# FinalUSB.net
KiCad netlist of a schematic drawn in EasyEDA Pro
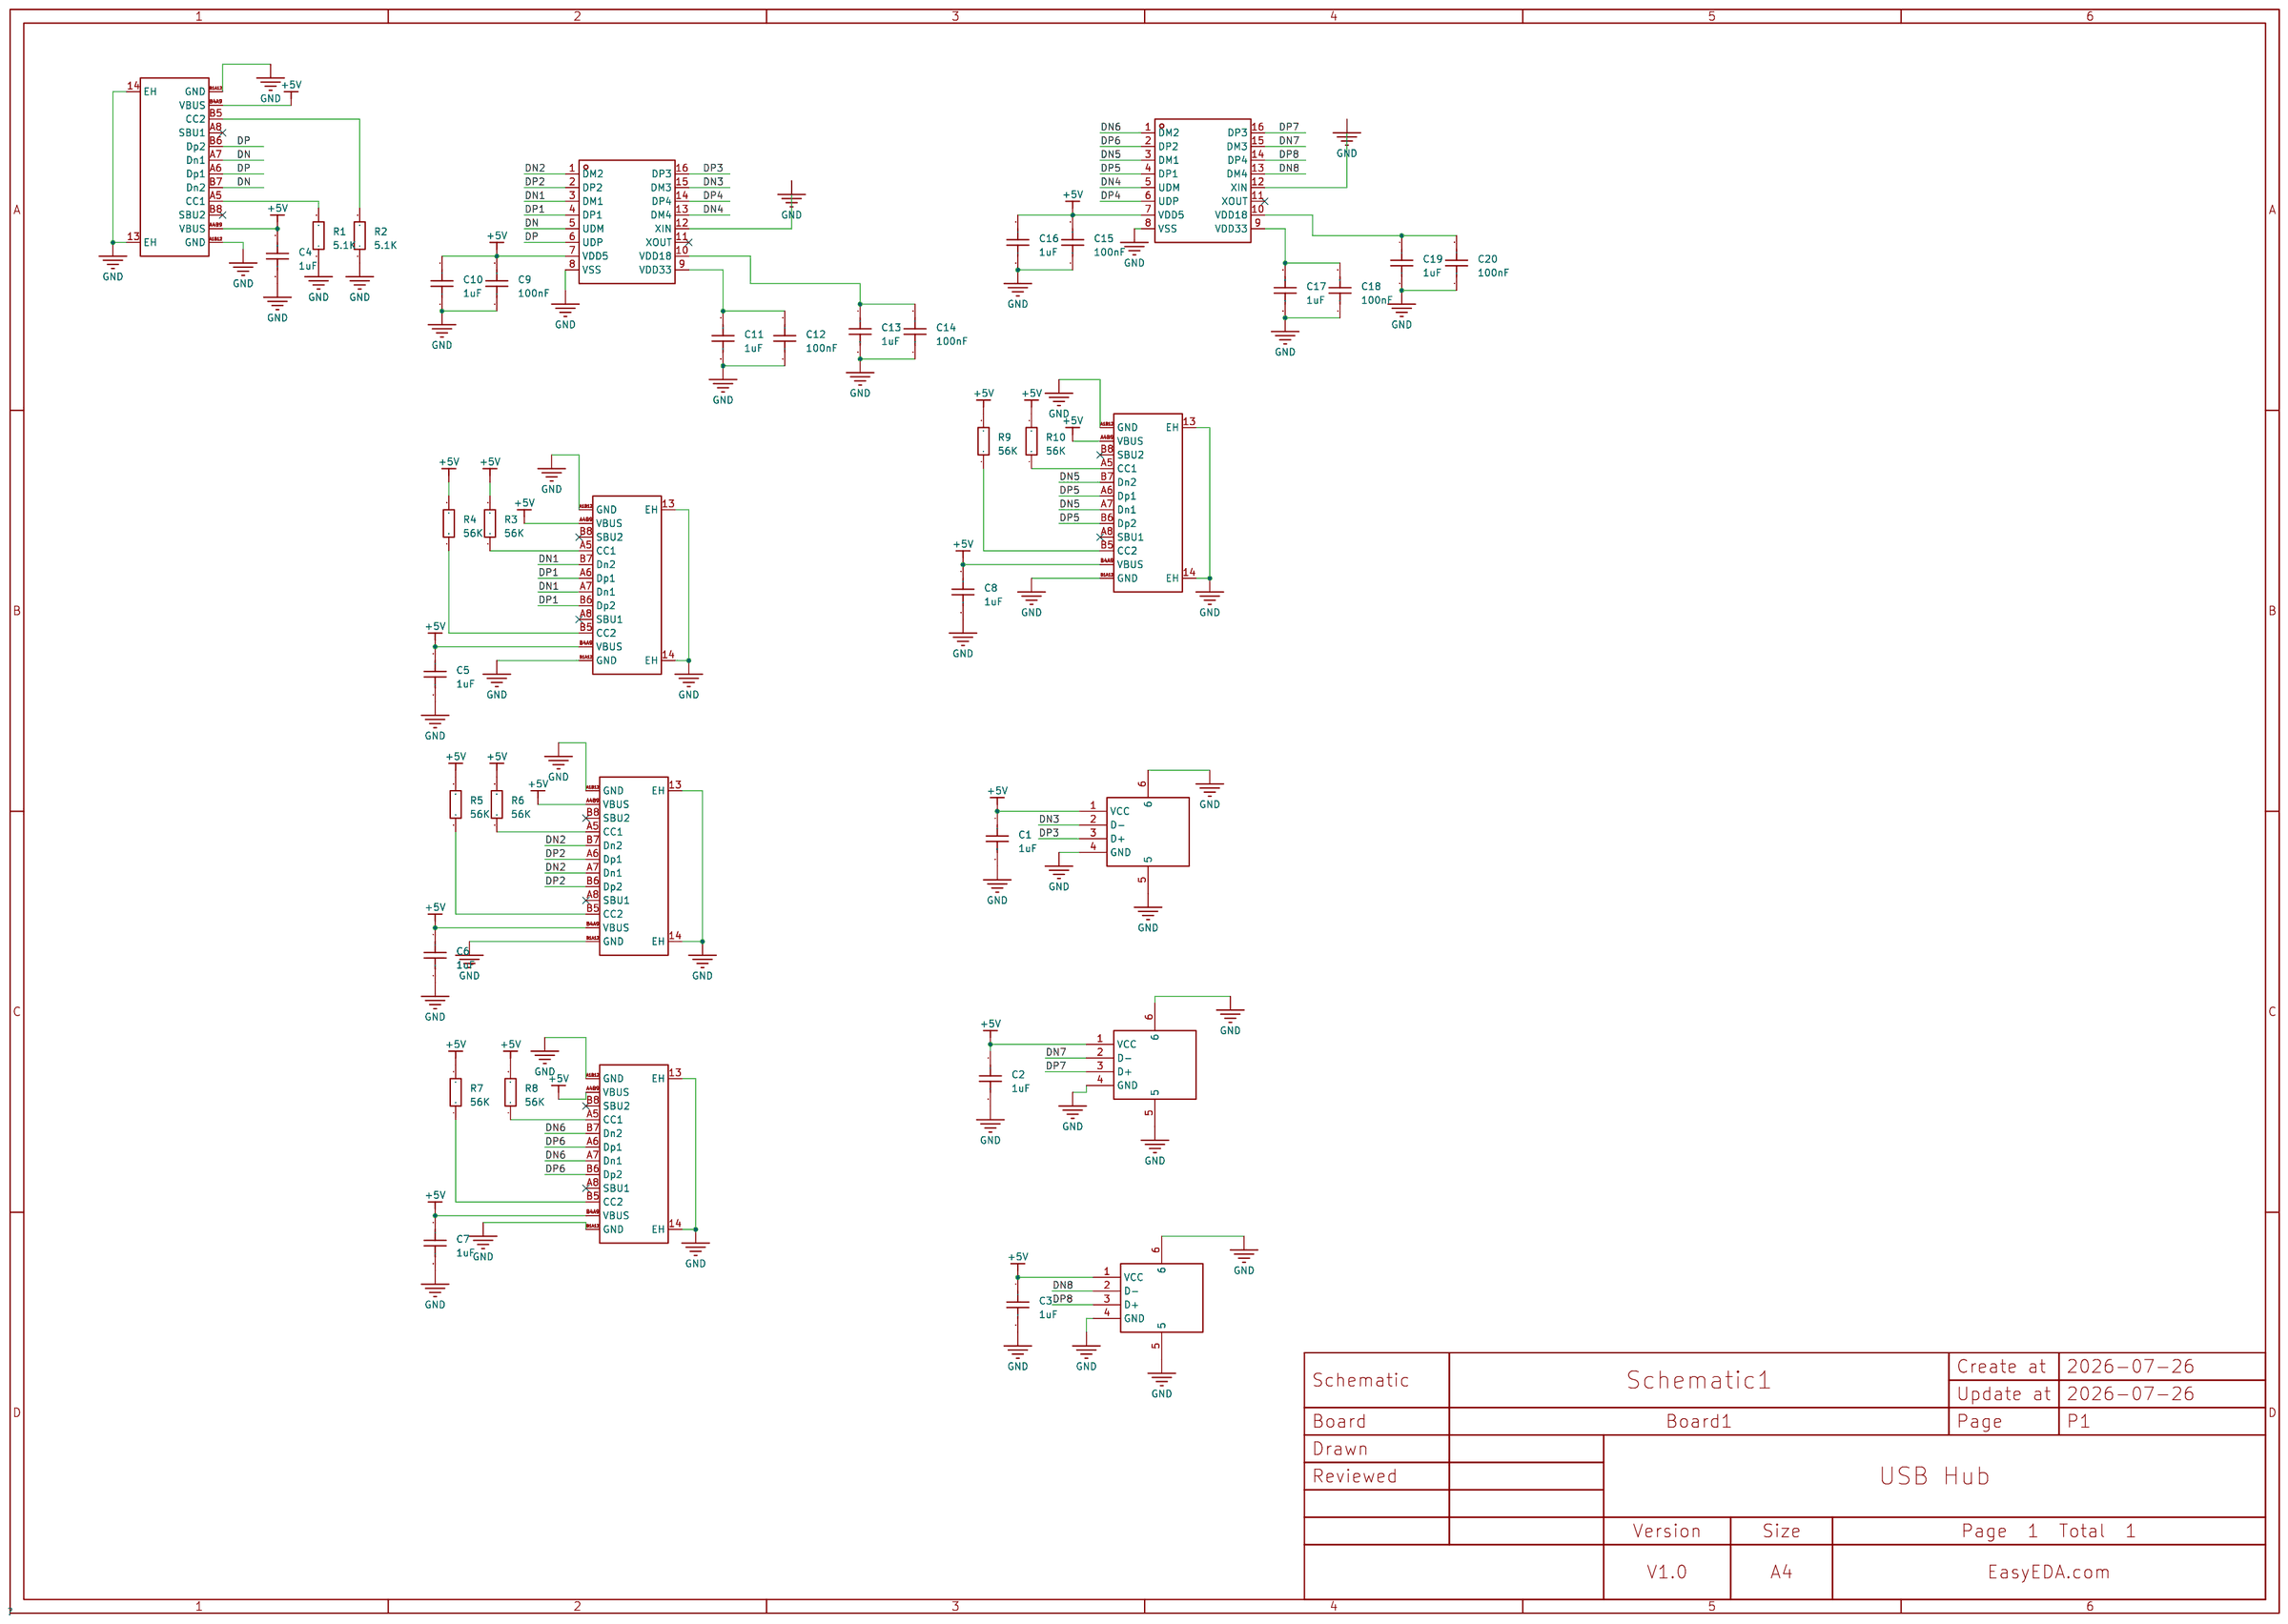
[diagram p0: schematic sheet]

(export (version "E")
  (design (tool "Eeschema 10.0.6"))
  (components
    (comp (ref "C1")
      (value "1uF")
      (footprint "easyedapro:C0603")
      (libsource (lib "easyedapro") (part "CAP_OLD"))
    )
    (comp (ref "C2")
      (value "1uF")
      (footprint "easyedapro:C0603")
      (libsource (lib "easyedapro") (part "CAP_OLD"))
    )
    (comp (ref "C3")
      (value "1uF")
      (footprint "easyedapro:C0603")
      (libsource (lib "easyedapro") (part "CAP_OLD"))
    )
    (comp (ref "C4")
      (value "1uF")
      (footprint "easyedapro:C0603")
      (libsource (lib "easyedapro") (part "CAP_OLD"))
    )
    (comp (ref "C5")
      (value "1uF")
      (footprint "easyedapro:C0603")
      (libsource (lib "easyedapro") (part "CAP_OLD"))
    )
    (comp (ref "C6")
      (value "1uF")
      (footprint "easyedapro:C0603")
      (libsource (lib "easyedapro") (part "CAP_OLD"))
    )
    (comp (ref "C7")
      (value "1uF")
      (footprint "easyedapro:C0603")
      (libsource (lib "easyedapro") (part "CAP_OLD"))
    )
    (comp (ref "C8")
      (value "1uF")
      (footprint "easyedapro:C0603")
      (libsource (lib "easyedapro") (part "CAP_OLD"))
    )
    (comp (ref "C9")
      (value "100nF")
      (footprint "easyedapro:C0603")
      (libsource (lib "easyedapro") (part "CAP_OLD"))
    )
    (comp (ref "C10")
      (value "1uF")
      (footprint "easyedapro:C0603")
      (libsource (lib "easyedapro") (part "CAP_OLD"))
    )
    (comp (ref "C11")
      (value "1uF")
      (footprint "easyedapro:C0603")
      (libsource (lib "easyedapro") (part "CAP_OLD"))
    )
    (comp (ref "C12")
      (value "100nF")
      (footprint "easyedapro:C0603")
      (libsource (lib "easyedapro") (part "CAP_OLD"))
    )
    (comp (ref "C13")
      (value "1uF")
      (footprint "easyedapro:C0603")
      (libsource (lib "easyedapro") (part "CAP_OLD"))
    )
    (comp (ref "C14")
      (value "100nF")
      (footprint "easyedapro:C0603")
      (libsource (lib "easyedapro") (part "CAP_OLD"))
    )
    (comp (ref "C15")
      (value "100nF")
      (footprint "easyedapro:C0603")
      (libsource (lib "easyedapro") (part "CAP_OLD"))
    )
    (comp (ref "C16")
      (value "1uF")
      (footprint "easyedapro:C0603")
      (libsource (lib "easyedapro") (part "CAP_OLD"))
    )
    (comp (ref "C17")
      (value "1uF")
      (footprint "easyedapro:C0603")
      (libsource (lib "easyedapro") (part "CAP_OLD"))
    )
    (comp (ref "C18")
      (value "100nF")
      (footprint "easyedapro:C0603")
      (libsource (lib "easyedapro") (part "CAP_OLD"))
    )
    (comp (ref "C19")
      (value "1uF")
      (footprint "easyedapro:C0603")
      (libsource (lib "easyedapro") (part "CAP_OLD"))
    )
    (comp (ref "C20")
      (value "100nF")
      (footprint "easyedapro:C0603")
      (libsource (lib "easyedapro") (part "CAP_OLD"))
    )
    (comp (ref "R1")
      (value "5.1K")
      (footprint "easyedapro:R0603")
      (libsource (lib "easyedapro") (part "Res"))
    )
    (comp (ref "R2")
      (value "5.1K")
      (footprint "easyedapro:R0603")
      (libsource (lib "easyedapro") (part "Res"))
    )
    (comp (ref "R3") (value "56K") (footprint "easyedapro:R0603") (libsource (lib "easyedapro") (part "Res")))
    (comp (ref "R4") (value "56K") (footprint "easyedapro:R0603") (libsource (lib "easyedapro") (part "Res")))
    (comp (ref "R5") (value "56K") (footprint "easyedapro:R0603") (libsource (lib "easyedapro") (part "Res")))
    (comp (ref "R6") (value "56K") (footprint "easyedapro:R0603") (libsource (lib "easyedapro") (part "Res")))
    (comp (ref "R7") (value "56K") (footprint "easyedapro:R0603") (libsource (lib "easyedapro") (part "Res")))
    (comp (ref "R8") (value "56K") (footprint "easyedapro:R0603") (libsource (lib "easyedapro") (part "Res")))
    (comp (ref "R9") (value "56K") (footprint "easyedapro:R0603") (libsource (lib "easyedapro") (part "Res")))
    (comp (ref "R10")
      (value "56K")
      (footprint "easyedapro:R0603")
      (libsource (lib "easyedapro") (part "Res"))
    )
    (comp (ref "U1")
      (value "SL2.1s")
      (footprint "easyedapro:SSOP-16_L4.6-W2.6-P0.53-LS4.0-BL")
      (fields (field (name "Manufacturer") "CoreChips(和芯润德)"))
      (libsource (lib "easyedapro") (part "SL2.1S"))
    )
    (comp (ref "U2")
      (value "SL2.1s")
      (footprint "easyedapro:SSOP-16_L4.6-W2.6-P0.53-LS4.0-BL")
      (fields (field (name "Manufacturer") "CoreChips(和芯润德)"))
      (libsource (lib "easyedapro") (part "SL2.1S"))
    )
    (comp (ref "USB1")
      (value "TYPE-C 16PIN 2MD(073)")
      (footprint "easyedapro:USB-C-SMD_TYPE-C-16PIN-2MD-073")
      (fields (field (name "Manufacturer") "SHOU HAN(首韩)"))
      (libsource (lib "easyedapro") (part "TYPE-C 16PIN 2MD(073)"))
    )
    (comp (ref "USB2")
      (value "TYPE-C 16PIN 2MD(073)")
      (footprint "easyedapro:USB-C-SMD_TYPE-C-16PIN-2MD-073")
      (fields (field (name "Manufacturer") "SHOU HAN(首韩)"))
      (libsource (lib "easyedapro") (part "TYPE-C 16PIN 2MD(073)"))
    )
    (comp (ref "USB3")
      (value "TYPE-C 16PIN 2MD(073)")
      (footprint "easyedapro:USB-C-SMD_TYPE-C-16PIN-2MD-073")
      (fields (field (name "Manufacturer") "SHOU HAN(首韩)"))
      (libsource (lib "easyedapro") (part "TYPE-C 16PIN 2MD(073)"))
    )
    (comp (ref "USB4")
      (value "10.0 QHHTZB6.3")
      (footprint "easyedapro:USB-A-TH_10.0QHHTZB6.3")
      (fields (field (name "Manufacturer") "SHOU HAN(首韩)"))
      (libsource (lib "easyedapro") (part "10.0 QHHTZB6.3"))
    )
    (comp (ref "USB5")
      (value "TYPE-C 16PIN 2MD(073)")
      (footprint "easyedapro:USB-C-SMD_TYPE-C-16PIN-2MD-073")
      (fields (field (name "Manufacturer") "SHOU HAN(首韩)"))
      (libsource (lib "easyedapro") (part "TYPE-C 16PIN 2MD(073)"))
    )
    (comp (ref "USB6")
      (value "10.0 QHHTZB6.3")
      (footprint "easyedapro:USB-A-TH_10.0QHHTZB6.3")
      (fields (field (name "Manufacturer") "SHOU HAN(首韩)"))
      (libsource (lib "easyedapro") (part "10.0 QHHTZB6.3"))
    )
    (comp (ref "USB7")
      (value "TYPE-C 16PIN 2MD(073)")
      (footprint "easyedapro:USB-C-SMD_TYPE-C-16PIN-2MD-073")
      (fields (field (name "Manufacturer") "SHOU HAN(首韩)"))
      (libsource (lib "easyedapro") (part "TYPE-C 16PIN 2MD(073)"))
    )
    (comp (ref "USB8")
      (value "10.0 QHHTZB6.3")
      (footprint "easyedapro:USB-A-TH_10.0QHHTZB6.3")
      (fields (field (name "Manufacturer") "SHOU HAN(首韩)"))
      (libsource (lib "easyedapro") (part "10.0 QHHTZB6.3"))
    )
  )
  (nets
    (net (code "1") (name "+5V") (class "Default")
      (node (ref "C1") (pin "1") (pinfunction "1_1") (pintype "input"))
      (node (ref "C10") (pin "1") (pinfunction "1_1") (pintype "input"))
      (node (ref "C15") (pin "2") (pinfunction "2_2") (pintype "input"))
      (node (ref "C16") (pin "1") (pinfunction "1_1") (pintype "input"))
      (node (ref "C2") (pin "1") (pinfunction "1_1") (pintype "input"))
      (node (ref "C3") (pin "1") (pinfunction "1_1") (pintype "input"))
      (node (ref "C4") (pin "1") (pinfunction "1_1") (pintype "input"))
      (node (ref "C5") (pin "1") (pinfunction "1_1") (pintype "input"))
      (node (ref "C6") (pin "1") (pinfunction "1_1") (pintype "input"))
      (node (ref "C7") (pin "1") (pinfunction "1_1") (pintype "input"))
      (node (ref "C8") (pin "1") (pinfunction "1_1") (pintype "input"))
      (node (ref "C9") (pin "2") (pinfunction "2_2") (pintype "input"))
      (node (ref "R10") (pin "2") (pinfunction "2_2") (pintype "input"))
      (node (ref "R3") (pin "2") (pinfunction "2_2") (pintype "input"))
      (node (ref "R4") (pin "2") (pinfunction "2_2") (pintype "input"))
      (node (ref "R5") (pin "2") (pinfunction "2_2") (pintype "input"))
      (node (ref "R6") (pin "2") (pinfunction "2_2") (pintype "input"))
      (node (ref "R7") (pin "2") (pinfunction "2_2") (pintype "input"))
      (node (ref "R8") (pin "2") (pinfunction "2_2") (pintype "input"))
      (node (ref "R9") (pin "2") (pinfunction "2_2") (pintype "input"))
      (node (ref "U1") (pin "7") (pinfunction "VDD5_7") (pintype "unspecified"))
      (node (ref "U2") (pin "7") (pinfunction "VDD5_7") (pintype "unspecified"))
      (node (ref "USB1") (pin "A4B9") (pinfunction "VBUS_A4B9") (pintype "unspecified"))
      (node (ref "USB1") (pin "B4A9") (pinfunction "VBUS_B4A9") (pintype "unspecified"))
      (node (ref "USB2") (pin "A4B9") (pinfunction "VBUS_A4B9") (pintype "unspecified"))
      (node (ref "USB2") (pin "B4A9") (pinfunction "VBUS_B4A9") (pintype "unspecified"))
      (node (ref "USB3") (pin "A4B9") (pinfunction "VBUS_A4B9") (pintype "unspecified"))
      (node (ref "USB3") (pin "B4A9") (pinfunction "VBUS_B4A9") (pintype "unspecified"))
      (node (ref "USB4") (pin "1") (pinfunction "VCC_1") (pintype "unspecified"))
      (node (ref "USB5") (pin "A4B9") (pinfunction "VBUS_A4B9") (pintype "unspecified"))
      (node (ref "USB5") (pin "B4A9") (pinfunction "VBUS_B4A9") (pintype "unspecified"))
      (node (ref "USB6") (pin "1") (pinfunction "VCC_1") (pintype "unspecified"))
      (node (ref "USB7") (pin "A4B9") (pinfunction "VBUS_A4B9") (pintype "unspecified"))
      (node (ref "USB7") (pin "B4A9") (pinfunction "VBUS_B4A9") (pintype "unspecified"))
      (node (ref "USB8") (pin "1") (pinfunction "VCC_1") (pintype "unspecified"))
    )
    (net (code "2") (name "/DN") (class "Default")
      (node (ref "U1") (pin "5") (pinfunction "UDM_5") (pintype "unspecified"))
      (node (ref "USB5") (pin "A7") (pinfunction "Dn1_A7") (pintype "unspecified"))
      (node (ref "USB5") (pin "B7") (pinfunction "Dn2_B7") (pintype "unspecified"))
    )
    (net (code "3") (name "/DN1") (class "Default")
      (node (ref "U1") (pin "3") (pinfunction "DM1_3") (pintype "unspecified"))
      (node (ref "USB1") (pin "A7") (pinfunction "Dn1_A7") (pintype "unspecified"))
      (node (ref "USB1") (pin "B7") (pinfunction "Dn2_B7") (pintype "unspecified"))
    )
    (net (code "4") (name "/DN2") (class "Default")
      (node (ref "U1") (pin "1") (pinfunction "DM2_1") (pintype "unspecified"))
      (node (ref "USB2") (pin "A7") (pinfunction "Dn1_A7") (pintype "unspecified"))
      (node (ref "USB2") (pin "B7") (pinfunction "Dn2_B7") (pintype "unspecified"))
    )
    (net (code "5") (name "/DN3") (class "Default")
      (node (ref "U1") (pin "15") (pinfunction "DM3_15") (pintype "unspecified"))
      (node (ref "USB6") (pin "2") (pinfunction "D-_2") (pintype "unspecified"))
    )
    (net (code "6") (name "/DN4") (class "Default")
      (node (ref "U1") (pin "13") (pinfunction "DM4_13") (pintype "unspecified"))
      (node (ref "U2") (pin "5") (pinfunction "UDM_5") (pintype "unspecified"))
    )
    (net (code "7") (name "/DN5") (class "Default")
      (node (ref "U2") (pin "3") (pinfunction "DM1_3") (pintype "unspecified"))
      (node (ref "USB7") (pin "A7") (pinfunction "Dn1_A7") (pintype "unspecified"))
      (node (ref "USB7") (pin "B7") (pinfunction "Dn2_B7") (pintype "unspecified"))
    )
    (net (code "8") (name "/DN6") (class "Default")
      (node (ref "U2") (pin "1") (pinfunction "DM2_1") (pintype "unspecified"))
      (node (ref "USB3") (pin "A7") (pinfunction "Dn1_A7") (pintype "unspecified"))
      (node (ref "USB3") (pin "B7") (pinfunction "Dn2_B7") (pintype "unspecified"))
    )
    (net (code "9") (name "/DN7") (class "Default")
      (node (ref "U2") (pin "15") (pinfunction "DM3_15") (pintype "unspecified"))
      (node (ref "USB4") (pin "2") (pinfunction "D-_2") (pintype "unspecified"))
    )
    (net (code "10") (name "/DN8") (class "Default")
      (node (ref "U2") (pin "13") (pinfunction "DM4_13") (pintype "unspecified"))
      (node (ref "USB8") (pin "2") (pinfunction "D-_2") (pintype "unspecified"))
    )
    (net (code "11") (name "/DP") (class "Default")
      (node (ref "U1") (pin "6") (pinfunction "UDP_6") (pintype "unspecified"))
      (node (ref "USB5") (pin "A6") (pinfunction "Dp1_A6") (pintype "unspecified"))
      (node (ref "USB5") (pin "B6") (pinfunction "Dp2_B6") (pintype "unspecified"))
    )
    (net (code "12") (name "/DP1") (class "Default")
      (node (ref "U1") (pin "4") (pinfunction "DP1_4") (pintype "unspecified"))
      (node (ref "USB1") (pin "A6") (pinfunction "Dp1_A6") (pintype "unspecified"))
      (node (ref "USB1") (pin "B6") (pinfunction "Dp2_B6") (pintype "unspecified"))
    )
    (net (code "13") (name "/DP2") (class "Default")
      (node (ref "U1") (pin "2") (pinfunction "DP2_2") (pintype "unspecified"))
      (node (ref "USB2") (pin "A6") (pinfunction "Dp1_A6") (pintype "unspecified"))
      (node (ref "USB2") (pin "B6") (pinfunction "Dp2_B6") (pintype "unspecified"))
    )
    (net (code "14") (name "/DP3") (class "Default")
      (node (ref "U1") (pin "16") (pinfunction "DP3_16") (pintype "unspecified"))
      (node (ref "USB6") (pin "3") (pinfunction "D+_3") (pintype "unspecified"))
    )
    (net (code "15") (name "/DP4") (class "Default")
      (node (ref "U1") (pin "14") (pinfunction "DP4_14") (pintype "unspecified"))
      (node (ref "U2") (pin "6") (pinfunction "UDP_6") (pintype "unspecified"))
    )
    (net (code "16") (name "/DP5") (class "Default")
      (node (ref "U2") (pin "4") (pinfunction "DP1_4") (pintype "unspecified"))
      (node (ref "USB7") (pin "A6") (pinfunction "Dp1_A6") (pintype "unspecified"))
      (node (ref "USB7") (pin "B6") (pinfunction "Dp2_B6") (pintype "unspecified"))
    )
    (net (code "17") (name "/DP6") (class "Default")
      (node (ref "U2") (pin "2") (pinfunction "DP2_2") (pintype "unspecified"))
      (node (ref "USB3") (pin "A6") (pinfunction "Dp1_A6") (pintype "unspecified"))
      (node (ref "USB3") (pin "B6") (pinfunction "Dp2_B6") (pintype "unspecified"))
    )
    (net (code "18") (name "/DP7") (class "Default")
      (node (ref "U2") (pin "16") (pinfunction "DP3_16") (pintype "unspecified"))
      (node (ref "USB4") (pin "3") (pinfunction "D+_3") (pintype "unspecified"))
    )
    (net (code "19") (name "/DP8") (class "Default")
      (node (ref "U2") (pin "14") (pinfunction "DP4_14") (pintype "unspecified"))
      (node (ref "USB8") (pin "3") (pinfunction "D+_3") (pintype "unspecified"))
    )
    (net (code "20") (name "GND") (class "Default")
      (node (ref "C1") (pin "2") (pinfunction "2_2") (pintype "input"))
      (node (ref "C10") (pin "2") (pinfunction "2_2") (pintype "input"))
      (node (ref "C11") (pin "2") (pinfunction "2_2") (pintype "input"))
      (node (ref "C12") (pin "1") (pinfunction "1_1") (pintype "input"))
      (node (ref "C13") (pin "2") (pinfunction "2_2") (pintype "input"))
      (node (ref "C14") (pin "1") (pinfunction "1_1") (pintype "input"))
      (node (ref "C15") (pin "1") (pinfunction "1_1") (pintype "input"))
      (node (ref "C16") (pin "2") (pinfunction "2_2") (pintype "input"))
      (node (ref "C17") (pin "2") (pinfunction "2_2") (pintype "input"))
      (node (ref "C18") (pin "1") (pinfunction "1_1") (pintype "input"))
      (node (ref "C19") (pin "2") (pinfunction "2_2") (pintype "input"))
      (node (ref "C2") (pin "2") (pinfunction "2_2") (pintype "input"))
      (node (ref "C20") (pin "1") (pinfunction "1_1") (pintype "input"))
      (node (ref "C3") (pin "2") (pinfunction "2_2") (pintype "input"))
      (node (ref "C4") (pin "2") (pinfunction "2_2") (pintype "input"))
      (node (ref "C5") (pin "2") (pinfunction "2_2") (pintype "input"))
      (node (ref "C6") (pin "2") (pinfunction "2_2") (pintype "input"))
      (node (ref "C7") (pin "2") (pinfunction "2_2") (pintype "input"))
      (node (ref "C8") (pin "2") (pinfunction "2_2") (pintype "input"))
      (node (ref "C9") (pin "1") (pinfunction "1_1") (pintype "input"))
      (node (ref "R1") (pin "1") (pinfunction "1_1") (pintype "input"))
      (node (ref "R2") (pin "1") (pinfunction "1_1") (pintype "input"))
      (node (ref "U1") (pin "12") (pinfunction "XIN_12") (pintype "unspecified"))
      (node (ref "U1") (pin "8") (pinfunction "VSS_8") (pintype "unspecified"))
      (node (ref "U2") (pin "12") (pinfunction "XIN_12") (pintype "unspecified"))
      (node (ref "U2") (pin "8") (pinfunction "VSS_8") (pintype "unspecified"))
      (node (ref "USB1") (pin "13") (pinfunction "EH_13") (pintype "unspecified"))
      (node (ref "USB1") (pin "14") (pinfunction "EH_14") (pintype "unspecified"))
      (node (ref "USB1") (pin "A1B12") (pinfunction "GND_A1B12") (pintype "unspecified"))
      (node (ref "USB1") (pin "B1A12") (pinfunction "GND_B1A12") (pintype "unspecified"))
      (node (ref "USB2") (pin "13") (pinfunction "EH_13") (pintype "unspecified"))
      (node (ref "USB2") (pin "14") (pinfunction "EH_14") (pintype "unspecified"))
      (node (ref "USB2") (pin "A1B12") (pinfunction "GND_A1B12") (pintype "unspecified"))
      (node (ref "USB2") (pin "B1A12") (pinfunction "GND_B1A12") (pintype "unspecified"))
      (node (ref "USB3") (pin "13") (pinfunction "EH_13") (pintype "unspecified"))
      (node (ref "USB3") (pin "14") (pinfunction "EH_14") (pintype "unspecified"))
      (node (ref "USB3") (pin "A1B12") (pinfunction "GND_A1B12") (pintype "unspecified"))
      (node (ref "USB3") (pin "B1A12") (pinfunction "GND_B1A12") (pintype "unspecified"))
      (node (ref "USB4") (pin "4") (pinfunction "GND_4") (pintype "unspecified"))
      (node (ref "USB4") (pin "5") (pinfunction "5_5") (pintype "unspecified"))
      (node (ref "USB4") (pin "6") (pinfunction "6_6") (pintype "unspecified"))
      (node (ref "USB5") (pin "13") (pinfunction "EH_13") (pintype "unspecified"))
      (node (ref "USB5") (pin "14") (pinfunction "EH_14") (pintype "unspecified"))
      (node (ref "USB5") (pin "A1B12") (pinfunction "GND_A1B12") (pintype "unspecified"))
      (node (ref "USB5") (pin "B1A12") (pinfunction "GND_B1A12") (pintype "unspecified"))
      (node (ref "USB6") (pin "4") (pinfunction "GND_4") (pintype "unspecified"))
      (node (ref "USB6") (pin "5") (pinfunction "5_5") (pintype "unspecified"))
      (node (ref "USB6") (pin "6") (pinfunction "6_6") (pintype "unspecified"))
      (node (ref "USB7") (pin "13") (pinfunction "EH_13") (pintype "unspecified"))
      (node (ref "USB7") (pin "14") (pinfunction "EH_14") (pintype "unspecified"))
      (node (ref "USB7") (pin "A1B12") (pinfunction "GND_A1B12") (pintype "unspecified"))
      (node (ref "USB7") (pin "B1A12") (pinfunction "GND_B1A12") (pintype "unspecified"))
      (node (ref "USB8") (pin "4") (pinfunction "GND_4") (pintype "unspecified"))
      (node (ref "USB8") (pin "5") (pinfunction "5_5") (pintype "unspecified"))
      (node (ref "USB8") (pin "6") (pinfunction "6_6") (pintype "unspecified"))
    )
    (net (code "21") (name "Net-(U1-VDD18)") (class "Default")
      (node (ref "C13") (pin "1") (pinfunction "1_1") (pintype "input"))
      (node (ref "C14") (pin "2") (pinfunction "2_2") (pintype "input"))
      (node (ref "U1") (pin "10") (pinfunction "VDD18_10") (pintype "unspecified"))
    )
    (net (code "22") (name "Net-(U1-VDD33)") (class "Default")
      (node (ref "C11") (pin "1") (pinfunction "1_1") (pintype "input"))
      (node (ref "C12") (pin "2") (pinfunction "2_2") (pintype "input"))
      (node (ref "U1") (pin "9") (pinfunction "VDD33_9") (pintype "unspecified"))
    )
    (net (code "23") (name "Net-(U2-VDD18)") (class "Default")
      (node (ref "C19") (pin "1") (pinfunction "1_1") (pintype "input"))
      (node (ref "C20") (pin "2") (pinfunction "2_2") (pintype "input"))
      (node (ref "U2") (pin "10") (pinfunction "VDD18_10") (pintype "unspecified"))
    )
    (net (code "24") (name "Net-(U2-VDD33)") (class "Default")
      (node (ref "C17") (pin "1") (pinfunction "1_1") (pintype "input"))
      (node (ref "C18") (pin "2") (pinfunction "2_2") (pintype "input"))
      (node (ref "U2") (pin "9") (pinfunction "VDD33_9") (pintype "unspecified"))
    )
    (net (code "25") (name "Net-(USB1-CC1)") (class "Default")
      (node (ref "R3") (pin "1") (pinfunction "1_1") (pintype "input"))
      (node (ref "USB1") (pin "A5") (pinfunction "CC1_A5") (pintype "unspecified"))
    )
    (net (code "26") (name "Net-(USB1-CC2)") (class "Default")
      (node (ref "R4") (pin "1") (pinfunction "1_1") (pintype "input"))
      (node (ref "USB1") (pin "B5") (pinfunction "CC2_B5") (pintype "unspecified"))
    )
    (net (code "27") (name "Net-(USB2-CC1)") (class "Default")
      (node (ref "R6") (pin "1") (pinfunction "1_1") (pintype "input"))
      (node (ref "USB2") (pin "A5") (pinfunction "CC1_A5") (pintype "unspecified"))
    )
    (net (code "28") (name "Net-(USB2-CC2)") (class "Default")
      (node (ref "R5") (pin "1") (pinfunction "1_1") (pintype "input"))
      (node (ref "USB2") (pin "B5") (pinfunction "CC2_B5") (pintype "unspecified"))
    )
    (net (code "29") (name "Net-(USB3-CC1)") (class "Default")
      (node (ref "R8") (pin "1") (pinfunction "1_1") (pintype "input"))
      (node (ref "USB3") (pin "A5") (pinfunction "CC1_A5") (pintype "unspecified"))
    )
    (net (code "30") (name "Net-(USB3-CC2)") (class "Default")
      (node (ref "R7") (pin "1") (pinfunction "1_1") (pintype "input"))
      (node (ref "USB3") (pin "B5") (pinfunction "CC2_B5") (pintype "unspecified"))
    )
    (net (code "31") (name "Net-(USB5-CC1)") (class "Default")
      (node (ref "R1") (pin "2") (pinfunction "2_2") (pintype "input"))
      (node (ref "USB5") (pin "A5") (pinfunction "CC1_A5") (pintype "unspecified"))
    )
    (net (code "32") (name "Net-(USB5-CC2)") (class "Default")
      (node (ref "R2") (pin "2") (pinfunction "2_2") (pintype "input"))
      (node (ref "USB5") (pin "B5") (pinfunction "CC2_B5") (pintype "unspecified"))
    )
    (net (code "33") (name "Net-(USB7-CC1)") (class "Default")
      (node (ref "R10") (pin "1") (pinfunction "1_1") (pintype "input"))
      (node (ref "USB7") (pin "A5") (pinfunction "CC1_A5") (pintype "unspecified"))
    )
    (net (code "34") (name "Net-(USB7-CC2)") (class "Default")
      (node (ref "R9") (pin "1") (pinfunction "1_1") (pintype "input"))
      (node (ref "USB7") (pin "B5") (pinfunction "CC2_B5") (pintype "unspecified"))
    )
    (net (code "35") (name "unconnected-(U1-XOUT-Pad11)") (class "Default")
      (node (ref "U1") (pin "11") (pinfunction "XOUT_11") (pintype "unspecified+no_connect"))
    )
    (net (code "36") (name "unconnected-(U2-XOUT-Pad11)") (class "Default")
      (node (ref "U2") (pin "11") (pinfunction "XOUT_11") (pintype "unspecified+no_connect"))
    )
    (net (code "37") (name "unconnected-(USB1-SBU1-PadA8)") (class "Default")
      (node (ref "USB1") (pin "A8") (pinfunction "SBU1_A8") (pintype "unspecified+no_connect"))
    )
    (net (code "38") (name "unconnected-(USB1-SBU2-PadB8)") (class "Default")
      (node (ref "USB1") (pin "B8") (pinfunction "SBU2_B8") (pintype "unspecified+no_connect"))
    )
    (net (code "39") (name "unconnected-(USB2-SBU1-PadA8)") (class "Default")
      (node (ref "USB2") (pin "A8") (pinfunction "SBU1_A8") (pintype "unspecified+no_connect"))
    )
    (net (code "40") (name "unconnected-(USB2-SBU2-PadB8)") (class "Default")
      (node (ref "USB2") (pin "B8") (pinfunction "SBU2_B8") (pintype "unspecified+no_connect"))
    )
    (net (code "41") (name "unconnected-(USB3-SBU1-PadA8)") (class "Default")
      (node (ref "USB3") (pin "A8") (pinfunction "SBU1_A8") (pintype "unspecified+no_connect"))
    )
    (net (code "42") (name "unconnected-(USB3-SBU2-PadB8)") (class "Default")
      (node (ref "USB3") (pin "B8") (pinfunction "SBU2_B8") (pintype "unspecified+no_connect"))
    )
    (net (code "43") (name "unconnected-(USB5-SBU1-PadA8)") (class "Default")
      (node (ref "USB5") (pin "A8") (pinfunction "SBU1_A8") (pintype "unspecified+no_connect"))
    )
    (net (code "44") (name "unconnected-(USB5-SBU2-PadB8)") (class "Default")
      (node (ref "USB5") (pin "B8") (pinfunction "SBU2_B8") (pintype "unspecified+no_connect"))
    )
    (net (code "45") (name "unconnected-(USB7-SBU1-PadA8)") (class "Default")
      (node (ref "USB7") (pin "A8") (pinfunction "SBU1_A8") (pintype "unspecified+no_connect"))
    )
    (net (code "46") (name "unconnected-(USB7-SBU2-PadB8)") (class "Default")
      (node (ref "USB7") (pin "B8") (pinfunction "SBU2_B8") (pintype "unspecified+no_connect"))
    )
  )
)
